# i2c1.net
KiCad netlist of a schematic drawn in Altium Designer
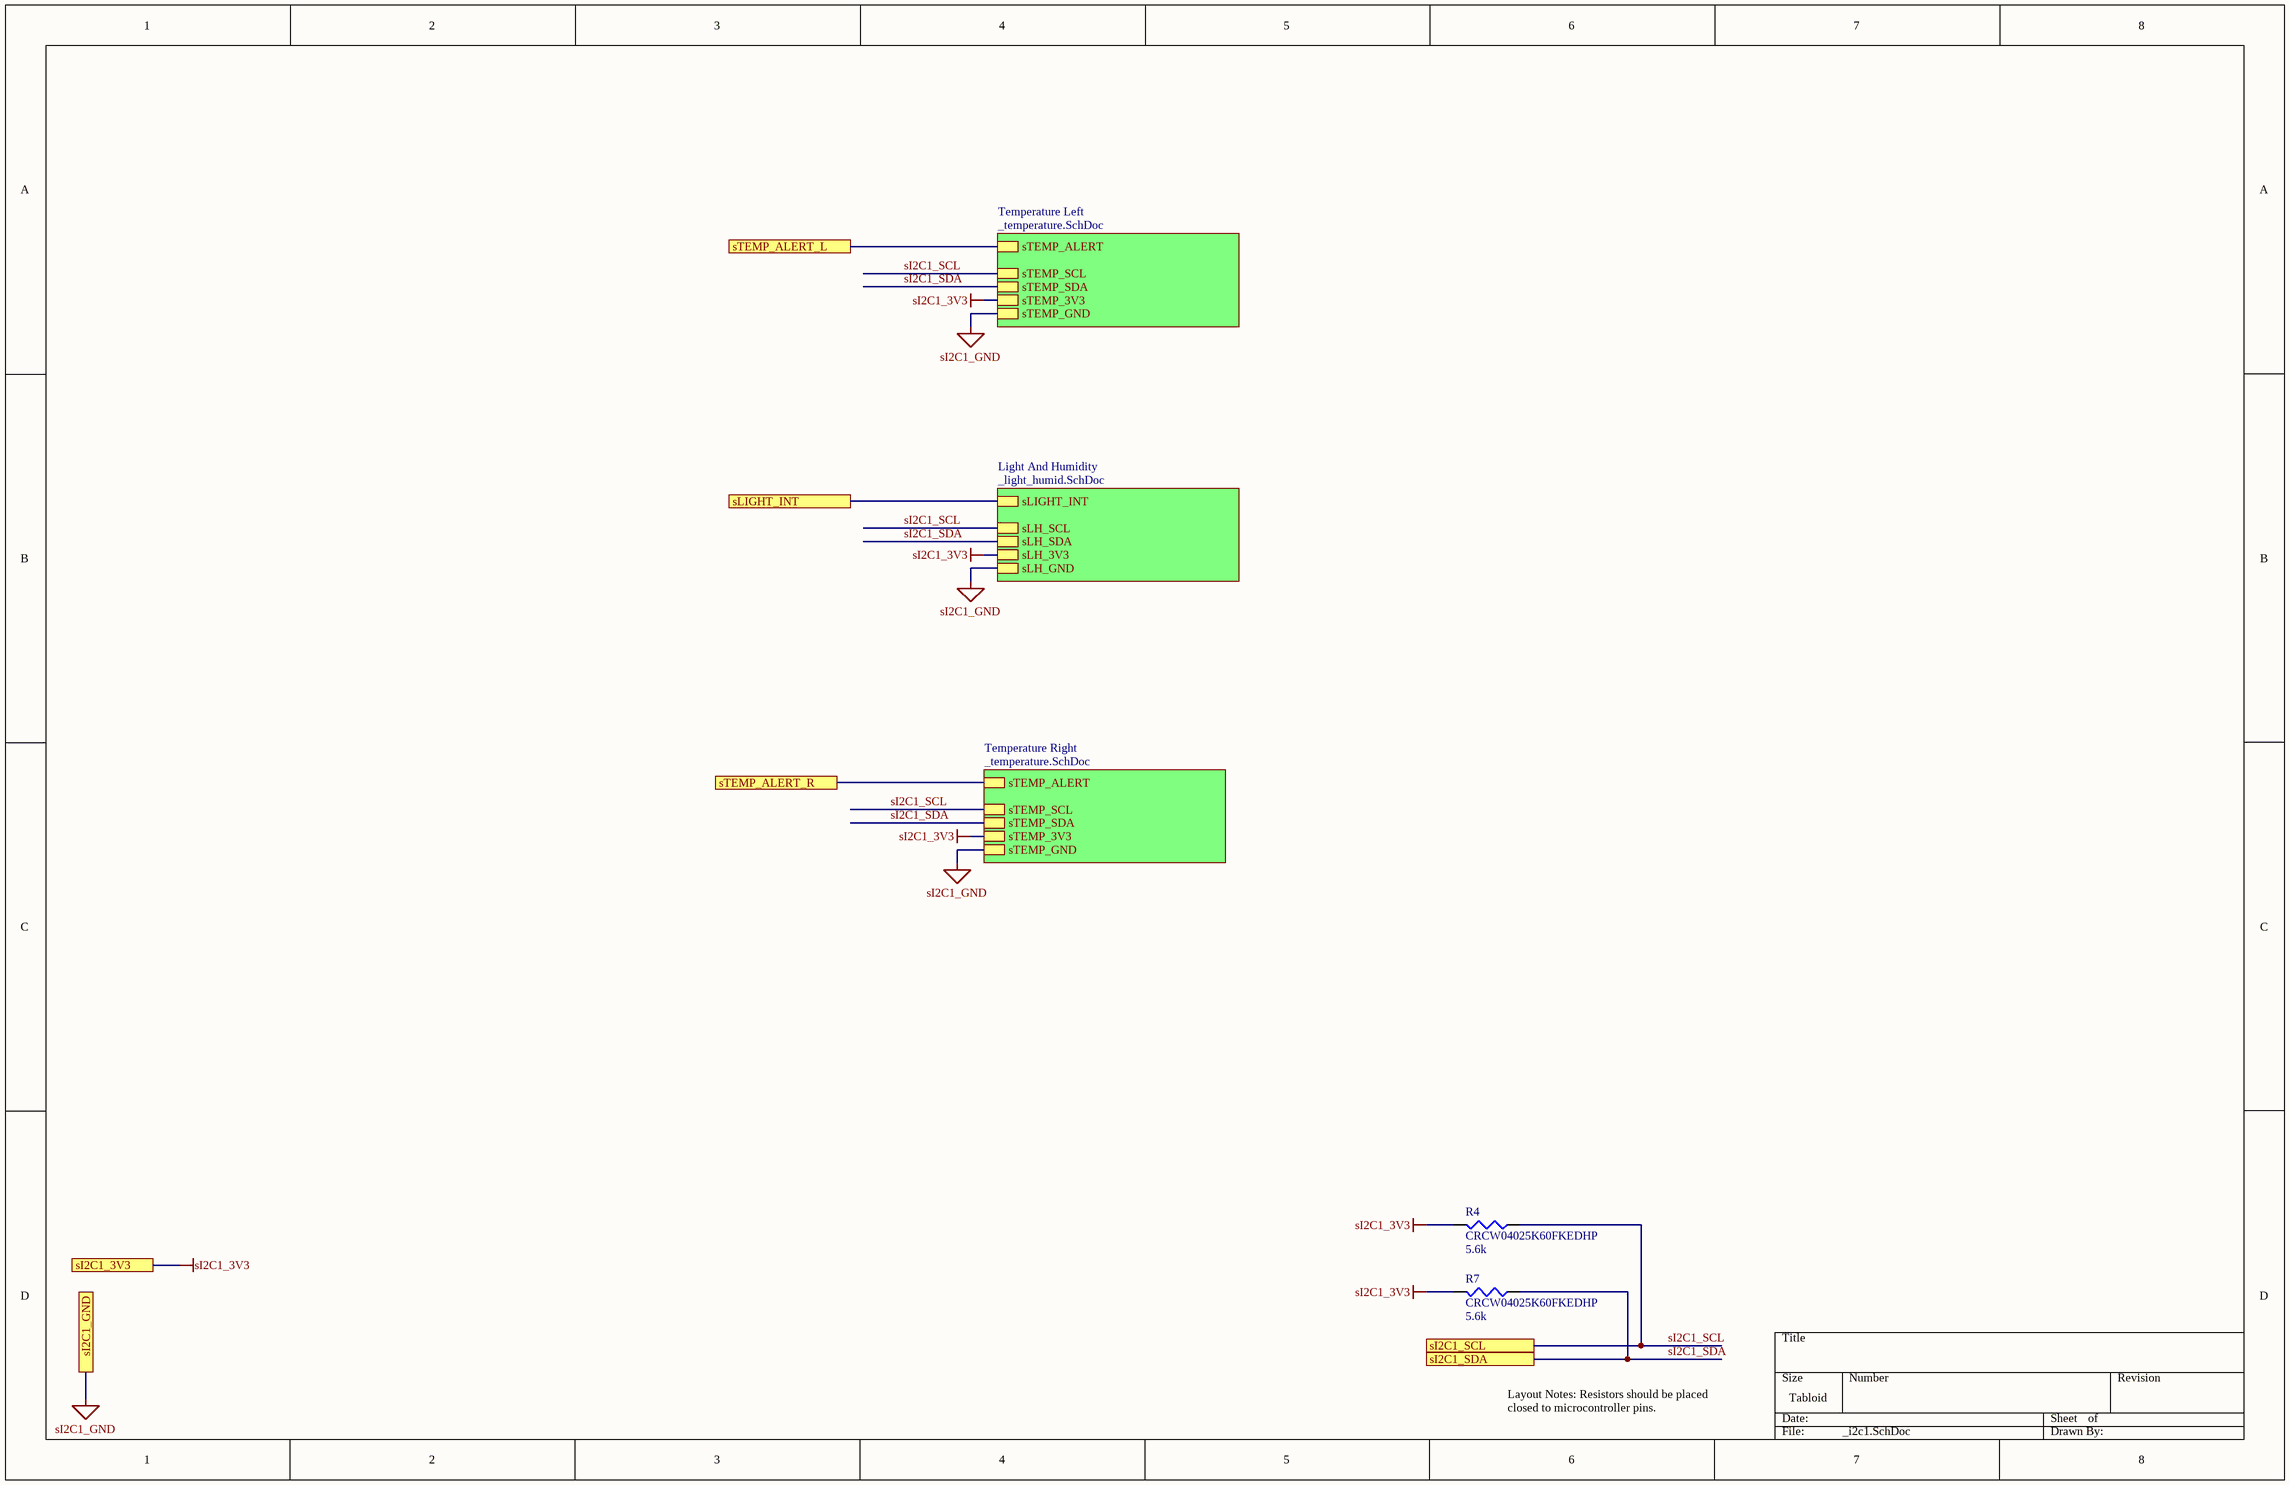
[diagram p0: _i2c1.SchDoc]

(export (version "E")
  (design (tool "Eeschema 10.0.6"))
  (components
    (comp (ref "R4")
      (value "CRCW04025K60FKEDHP")
      (footprint "0402")
      (description "0.125W, -55-155C, 1005, 50V, ±1%")
      (fields (field (name "ALTIUM_VALUE") "5.6k"))
      (libsource (lib "standard_resistors") (part "CRCW0402xxxxFKED"))
    )
    (comp (ref "R7")
      (value "CRCW04025K60FKEDHP")
      (footprint "0402")
      (description "0.125W, -55-155C, 1005, 50V, ±1%")
      (fields (field (name "ALTIUM_VALUE") "5.6k"))
      (libsource (lib "standard_resistors") (part "CRCW0402xxxxFKED"))
    )
  )
  (nets
    (net (code "1") (name "/sI2C1_SCL") (class "Default")
      (node (ref "R4") (pin "1") (pinfunction "1_1") (pintype "passive"))
    )
    (net (code "2") (name "/sI2C1_SDA") (class "Default")
      (node (ref "R7") (pin "1") (pinfunction "1_1") (pintype "passive"))
    )
    (net (code "6") (name "sI2C1_3V3") (class "Default")
      (node (ref "R4") (pin "2") (pinfunction "2_2") (pintype "passive"))
      (node (ref "R7") (pin "2") (pinfunction "2_2") (pintype "passive"))
    )
  )
)
